# canbus-proto2.net
KiCad netlist of a schematic drawn in EAGLE
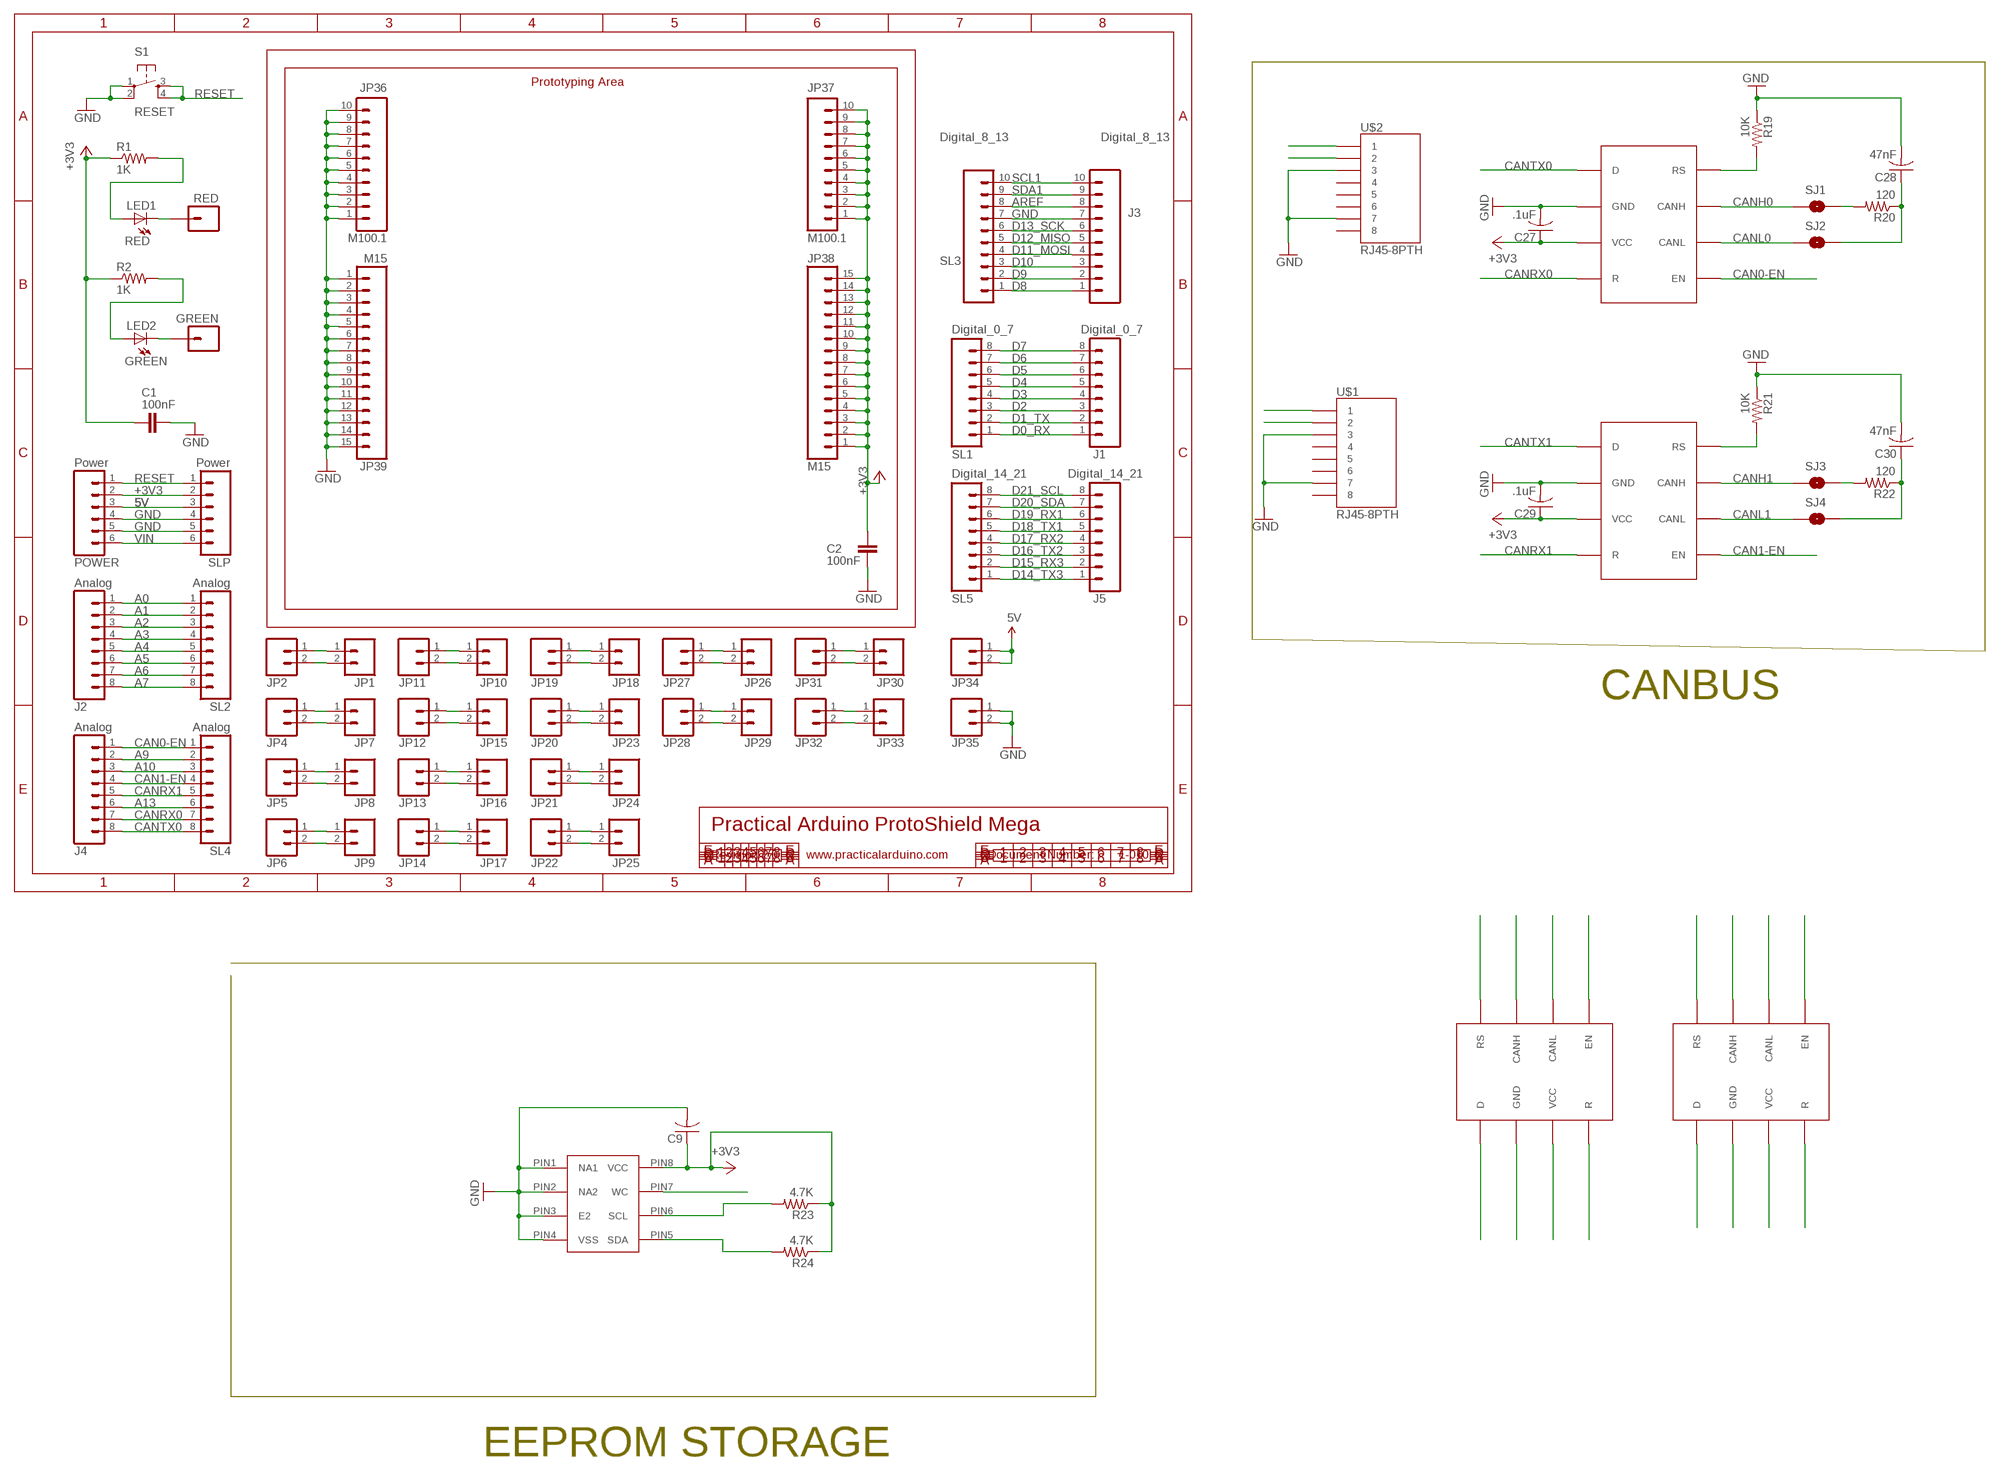
[diagram p0: schematic, sheet 1]

(export (version "E")
  (design (tool "Eeschema 10.0.6"))
  (components
    (comp (ref "C1")
      (value "100nF")
      (footprint "eagle-import:0603-CAP")
      (libsource (lib "eagle-import") (part "CAP0603-CAP"))
    )
    (comp (ref "C2")
      (value "100nF")
      (footprint "eagle-import:0603-CAP")
      (libsource (lib "eagle-import") (part "CAP0603-CAP"))
    )
    (comp (ref "C9")
      (value "C-USC0603")
      (footprint "eagle-import:C0603")
      (libsource (lib "eagle-import") (part "C-USC0603"))
    )
    (comp (ref "C27")
      (value ".1uF")
      (footprint "eagle-import:C0603")
      (libsource (lib "eagle-import") (part "C-USC0603"))
    )
    (comp (ref "C28")
      (value "47nF")
      (footprint "eagle-import:C0603")
      (libsource (lib "eagle-import") (part "C-USC0603"))
    )
    (comp (ref "C29")
      (value ".1uF")
      (footprint "eagle-import:C0603")
      (libsource (lib "eagle-import") (part "C-USC0603"))
    )
    (comp (ref "C30")
      (value "47nF")
      (footprint "eagle-import:C0603")
      (libsource (lib "eagle-import") (part "C-USC0603"))
    )
    (comp (ref "GREEN")
      (value "M01PTH")
      (footprint "eagle-import:1X01")
      (libsource (lib "eagle-import") (part "M01PTH"))
    )
    (comp (ref "J1")
      (value "Digital_0_7")
      (footprint "eagle-import:1X08")
      (libsource (lib "eagle-import") (part "M08"))
    )
    (comp (ref "J2")
      (value "Analog")
      (footprint "eagle-import:1X08")
      (libsource (lib "eagle-import") (part "M08"))
    )
    (comp (ref "J3")
      (value "Digital_8_13")
      (footprint "eagle-import:1X10")
      (libsource (lib "eagle-import") (part "M10{dblquote}"))
    )
    (comp (ref "J4")
      (value "Analog")
      (footprint "eagle-import:1X08")
      (libsource (lib "eagle-import") (part "M08"))
    )
    (comp (ref "J5")
      (value "Digital_14_21")
      (footprint "eagle-import:1X08")
      (libsource (lib "eagle-import") (part "M08"))
    )
    (comp (ref "JP1")
      (value "M02PTH")
      (footprint "eagle-import:1X02")
      (libsource (lib "eagle-import") (part "M02PTH"))
    )
    (comp (ref "JP2")
      (value "M02PTH")
      (footprint "eagle-import:1X02")
      (libsource (lib "eagle-import") (part "M02PTH"))
    )
    (comp (ref "JP4")
      (value "M02PTH")
      (footprint "eagle-import:1X02")
      (libsource (lib "eagle-import") (part "M02PTH"))
    )
    (comp (ref "JP5")
      (value "M02PTH")
      (footprint "eagle-import:1X02")
      (libsource (lib "eagle-import") (part "M02PTH"))
    )
    (comp (ref "JP6")
      (value "M02PTH")
      (footprint "eagle-import:1X02")
      (libsource (lib "eagle-import") (part "M02PTH"))
    )
    (comp (ref "JP7")
      (value "M02PTH")
      (footprint "eagle-import:1X02")
      (libsource (lib "eagle-import") (part "M02PTH"))
    )
    (comp (ref "JP8")
      (value "M02PTH")
      (footprint "eagle-import:1X02")
      (libsource (lib "eagle-import") (part "M02PTH"))
    )
    (comp (ref "JP9")
      (value "M02PTH")
      (footprint "eagle-import:1X02")
      (libsource (lib "eagle-import") (part "M02PTH"))
    )
    (comp (ref "JP10")
      (value "M02PTH")
      (footprint "eagle-import:1X02")
      (libsource (lib "eagle-import") (part "M02PTH"))
    )
    (comp (ref "JP11")
      (value "M02PTH")
      (footprint "eagle-import:1X02")
      (libsource (lib "eagle-import") (part "M02PTH"))
    )
    (comp (ref "JP12")
      (value "M02PTH")
      (footprint "eagle-import:1X02")
      (libsource (lib "eagle-import") (part "M02PTH"))
    )
    (comp (ref "JP13")
      (value "M02PTH")
      (footprint "eagle-import:1X02")
      (libsource (lib "eagle-import") (part "M02PTH"))
    )
    (comp (ref "JP14")
      (value "M02PTH")
      (footprint "eagle-import:1X02")
      (libsource (lib "eagle-import") (part "M02PTH"))
    )
    (comp (ref "JP15")
      (value "M02PTH")
      (footprint "eagle-import:1X02")
      (libsource (lib "eagle-import") (part "M02PTH"))
    )
    (comp (ref "JP16")
      (value "M02PTH")
      (footprint "eagle-import:1X02")
      (libsource (lib "eagle-import") (part "M02PTH"))
    )
    (comp (ref "JP17")
      (value "M02PTH")
      (footprint "eagle-import:1X02")
      (libsource (lib "eagle-import") (part "M02PTH"))
    )
    (comp (ref "JP18")
      (value "M02PTH")
      (footprint "eagle-import:1X02")
      (libsource (lib "eagle-import") (part "M02PTH"))
    )
    (comp (ref "JP19")
      (value "M02PTH")
      (footprint "eagle-import:1X02")
      (libsource (lib "eagle-import") (part "M02PTH"))
    )
    (comp (ref "JP20")
      (value "M02PTH")
      (footprint "eagle-import:1X02")
      (libsource (lib "eagle-import") (part "M02PTH"))
    )
    (comp (ref "JP21")
      (value "M02PTH")
      (footprint "eagle-import:1X02")
      (libsource (lib "eagle-import") (part "M02PTH"))
    )
    (comp (ref "JP22")
      (value "M02PTH")
      (footprint "eagle-import:1X02")
      (libsource (lib "eagle-import") (part "M02PTH"))
    )
    (comp (ref "JP23")
      (value "M02PTH")
      (footprint "eagle-import:1X02")
      (libsource (lib "eagle-import") (part "M02PTH"))
    )
    (comp (ref "JP24")
      (value "M02PTH")
      (footprint "eagle-import:1X02")
      (libsource (lib "eagle-import") (part "M02PTH"))
    )
    (comp (ref "JP25")
      (value "M02PTH")
      (footprint "eagle-import:1X02")
      (libsource (lib "eagle-import") (part "M02PTH"))
    )
    (comp (ref "JP26")
      (value "M02PTH")
      (footprint "eagle-import:1X02")
      (libsource (lib "eagle-import") (part "M02PTH"))
    )
    (comp (ref "JP27")
      (value "M02PTH")
      (footprint "eagle-import:1X02")
      (libsource (lib "eagle-import") (part "M02PTH"))
    )
    (comp (ref "JP28")
      (value "M02PTH")
      (footprint "eagle-import:1X02")
      (libsource (lib "eagle-import") (part "M02PTH"))
    )
    (comp (ref "JP29")
      (value "M02PTH")
      (footprint "eagle-import:1X02")
      (libsource (lib "eagle-import") (part "M02PTH"))
    )
    (comp (ref "JP30")
      (value "M02PTH")
      (footprint "eagle-import:1X02")
      (libsource (lib "eagle-import") (part "M02PTH"))
    )
    (comp (ref "JP31")
      (value "M02PTH")
      (footprint "eagle-import:1X02")
      (libsource (lib "eagle-import") (part "M02PTH"))
    )
    (comp (ref "JP32")
      (value "M02PTH")
      (footprint "eagle-import:1X02")
      (libsource (lib "eagle-import") (part "M02PTH"))
    )
    (comp (ref "JP33")
      (value "M02PTH")
      (footprint "eagle-import:1X02")
      (libsource (lib "eagle-import") (part "M02PTH"))
    )
    (comp (ref "JP34")
      (value "M02PTH")
      (footprint "eagle-import:1X02")
      (libsource (lib "eagle-import") (part "M02PTH"))
    )
    (comp (ref "JP35")
      (value "M02PTH")
      (footprint "eagle-import:1X02")
      (libsource (lib "eagle-import") (part "M02PTH"))
    )
    (comp (ref "JP36")
      (value "M100.1")
      (footprint "eagle-import:1X10@1")
      (libsource (lib "eagle-import") (part "M100.1"))
    )
    (comp (ref "JP37")
      (value "M100.1")
      (footprint "eagle-import:1X10@1")
      (libsource (lib "eagle-import") (part "M100.1"))
    )
    (comp (ref "JP38")
      (value "M15")
      (footprint "eagle-import:1X15")
      (libsource (lib "eagle-import") (part "M15"))
    )
    (comp (ref "JP39")
      (value "M15")
      (footprint "eagle-import:1X15")
      (libsource (lib "eagle-import") (part "M15"))
    )
    (comp (ref "LED1")
      (value "RED")
      (footprint "eagle-import:LED-0603")
      (libsource (lib "eagle-import") (part "LED-RED0603"))
    )
    (comp (ref "LED2")
      (value "GREEN")
      (footprint "eagle-import:LED-0603")
      (libsource (lib "eagle-import") (part "LED-GREEN0603"))
    )
    (comp (ref "POWER")
      (value "Power")
      (footprint "eagle-import:1X06")
      (libsource (lib "eagle-import") (part "M06SIP"))
    )
    (comp (ref "R1")
      (value "1K")
      (footprint "eagle-import:R0603")
      (libsource (lib "eagle-import") (part "R-US_R0603"))
    )
    (comp (ref "R2")
      (value "1K")
      (footprint "eagle-import:R0603")
      (libsource (lib "eagle-import") (part "R-US_R0603"))
    )
    (comp (ref "R19")
      (value "10K")
      (footprint "eagle-import:R0603")
      (libsource (lib "eagle-import") (part "R-US_R0603"))
    )
    (comp (ref "R20")
      (value "120")
      (footprint "eagle-import:R0603")
      (libsource (lib "eagle-import") (part "R-US_R0603"))
    )
    (comp (ref "R21")
      (value "10K")
      (footprint "eagle-import:R0603")
      (libsource (lib "eagle-import") (part "R-US_R0603"))
    )
    (comp (ref "R22")
      (value "120")
      (footprint "eagle-import:R0603")
      (libsource (lib "eagle-import") (part "R-US_R0603"))
    )
    (comp (ref "R23")
      (value "4.7K")
      (footprint "eagle-import:R0603")
      (libsource (lib "eagle-import") (part "R-US_R0603"))
    )
    (comp (ref "R24")
      (value "4.7K")
      (footprint "eagle-import:R0603")
      (libsource (lib "eagle-import") (part "R-US_R0603"))
    )
    (comp (ref "RED")
      (value "M01PTH")
      (footprint "eagle-import:1X01")
      (libsource (lib "eagle-import") (part "M01PTH"))
    )
    (comp (ref "S1")
      (value "RESET")
      (footprint "eagle-import:TACTILE-PTH")
      (libsource (lib "eagle-import") (part "TAC_SWITCHPTH"))
    )
    (comp (ref "SJ1")
      (value "SOLDERJUMPERNO")
      (footprint "eagle-import:SJ_2S-NO")
      (libsource (lib "eagle-import") (part "SOLDERJUMPERNO"))
    )
    (comp (ref "SJ2")
      (value "SOLDERJUMPERNO")
      (footprint "eagle-import:SJ_2S-NO")
      (libsource (lib "eagle-import") (part "SOLDERJUMPERNO"))
    )
    (comp (ref "SJ3")
      (value "SOLDERJUMPERNO")
      (footprint "eagle-import:SJ_2S-NO")
      (libsource (lib "eagle-import") (part "SOLDERJUMPERNO"))
    )
    (comp (ref "SJ4")
      (value "SOLDERJUMPERNO")
      (footprint "eagle-import:SJ_2S-NO")
      (libsource (lib "eagle-import") (part "SOLDERJUMPERNO"))
    )
    (comp (ref "SL1")
      (value "Digital_0_7")
      (footprint "eagle-import:1X08")
      (libsource (lib "eagle-import") (part "M08"))
    )
    (comp (ref "SL2")
      (value "Analog")
      (footprint "eagle-import:1X08")
      (libsource (lib "eagle-import") (part "M08"))
    )
    (comp (ref "SL3")
      (value "Digital_8_13")
      (footprint "eagle-import:1X10")
      (libsource (lib "eagle-import") (part "M10{dblquote}"))
    )
    (comp (ref "SL4")
      (value "Analog")
      (footprint "eagle-import:1X08")
      (libsource (lib "eagle-import") (part "M08"))
    )
    (comp (ref "SL5")
      (value "Digital_14_21")
      (footprint "eagle-import:1X08")
      (libsource (lib "eagle-import") (part "M08"))
    )
    (comp (ref "SLP")
      (value "Power")
      (footprint "eagle-import:1X06")
      (libsource (lib "eagle-import") (part "M06SIP"))
    )
    (comp (ref "U$1")
      (value "RJ45-8PTH")
      (footprint "eagle-import:RJ45-8")
      (libsource (lib "eagle-import") (part "RJ45-8PTH"))
    )
    (comp (ref "U$2")
      (value "RJ45-8PTH")
      (footprint "eagle-import:RJ45-8")
      (libsource (lib "eagle-import") (part "RJ45-8PTH"))
    )
    (comp (ref "U$3")
      (value "SN65HVD234")
      (footprint "eagle-import:SOIC8")
      (libsource (lib "eagle-import") (part "SN65HVD234"))
    )
    (comp (ref "U$4")
      (value "SN65HVD234")
      (footprint "eagle-import:SOIC8")
      (libsource (lib "eagle-import") (part "SN65HVD234"))
    )
    (comp (ref "U$6")
      (value "M24M02-DRMN6TP")
      (footprint "eagle-import:SOIC8")
      (libsource (lib "eagle-import") (part "M24M02-DRMN6TP"))
    )
    (comp (ref "U$7")
      (value "SN65HVD234")
      (footprint "eagle-import:SOIC8")
      (libsource (lib "eagle-import") (part "SN65HVD234"))
    )
    (comp (ref "U$8")
      (value "SN65HVD234")
      (footprint "eagle-import:SOIC8")
      (libsource (lib "eagle-import") (part "SN65HVD234"))
    )
  )
  (nets
    (net (code "1") (name "+3V3") (class "Default")
      (node (ref "C1") (pin "1") (pinfunction "1_1") (pintype "passive"))
      (node (ref "C2") (pin "1") (pinfunction "1_1") (pintype "passive"))
      (node (ref "C27") (pin "1") (pinfunction "1_1") (pintype "passive"))
      (node (ref "C29") (pin "1") (pinfunction "1_1") (pintype "passive"))
      (node (ref "C9") (pin "1") (pinfunction "1_1") (pintype "passive"))
      (node (ref "JP37") (pin "1") (pinfunction "1_1") (pintype "passive"))
      (node (ref "JP37") (pin "10") (pinfunction "10_10") (pintype "passive"))
      (node (ref "JP37") (pin "2") (pinfunction "2_2") (pintype "passive"))
      (node (ref "JP37") (pin "3") (pinfunction "3_3") (pintype "passive"))
      (node (ref "JP37") (pin "4") (pinfunction "4_4") (pintype "passive"))
      (node (ref "JP37") (pin "5") (pinfunction "5_5") (pintype "passive"))
      (node (ref "JP37") (pin "6") (pinfunction "6_6") (pintype "passive"))
      (node (ref "JP37") (pin "7") (pinfunction "7_7") (pintype "passive"))
      (node (ref "JP37") (pin "8") (pinfunction "8_8") (pintype "passive"))
      (node (ref "JP37") (pin "9") (pinfunction "9_9") (pintype "passive"))
      (node (ref "JP38") (pin "1") (pinfunction "1_1") (pintype "passive"))
      (node (ref "JP38") (pin "10") (pinfunction "10_10") (pintype "passive"))
      (node (ref "JP38") (pin "11") (pinfunction "11_11") (pintype "passive"))
      (node (ref "JP38") (pin "12") (pinfunction "12_12") (pintype "passive"))
      (node (ref "JP38") (pin "13") (pinfunction "13_13") (pintype "passive"))
      (node (ref "JP38") (pin "14") (pinfunction "14_14") (pintype "passive"))
      (node (ref "JP38") (pin "15") (pinfunction "15_15") (pintype "passive"))
      (node (ref "JP38") (pin "2") (pinfunction "2_2") (pintype "passive"))
      (node (ref "JP38") (pin "3") (pinfunction "3_3") (pintype "passive"))
      (node (ref "JP38") (pin "4") (pinfunction "4_4") (pintype "passive"))
      (node (ref "JP38") (pin "5") (pinfunction "5_5") (pintype "passive"))
      (node (ref "JP38") (pin "6") (pinfunction "6_6") (pintype "passive"))
      (node (ref "JP38") (pin "7") (pinfunction "7_7") (pintype "passive"))
      (node (ref "JP38") (pin "8") (pinfunction "8_8") (pintype "passive"))
      (node (ref "JP38") (pin "9") (pinfunction "9_9") (pintype "passive"))
      (node (ref "POWER") (pin "2") (pinfunction "2_2") (pintype "passive"))
      (node (ref "R1") (pin "1") (pinfunction "1_1") (pintype "passive"))
      (node (ref "R2") (pin "1") (pinfunction "1_1") (pintype "passive"))
      (node (ref "R23") (pin "1") (pinfunction "1_1") (pintype "passive"))
      (node (ref "R24") (pin "1") (pinfunction "1_1") (pintype "passive"))
      (node (ref "SLP") (pin "2") (pinfunction "2_2") (pintype "passive"))
      (node (ref "U$6") (pin "PIN8") (pinfunction "VCC_PIN8") (pintype "bidirectional"))
      (node (ref "U$7") (pin "PIN3") (pinfunction "VCC_PIN3") (pintype "bidirectional"))
      (node (ref "U$8") (pin "PIN3") (pinfunction "VCC_PIN3") (pintype "bidirectional"))
    )
    (net (code "2") (name "/A0") (class "Default")
      (node (ref "J2") (pin "1") (pinfunction "1_1") (pintype "passive"))
      (node (ref "SL2") (pin "1") (pinfunction "1_1") (pintype "passive"))
    )
    (net (code "3") (name "/A1") (class "Default")
      (node (ref "J2") (pin "2") (pinfunction "2_2") (pintype "passive"))
      (node (ref "SL2") (pin "2") (pinfunction "2_2") (pintype "passive"))
    )
    (net (code "4") (name "/A2") (class "Default")
      (node (ref "J2") (pin "3") (pinfunction "3_3") (pintype "passive"))
      (node (ref "SL2") (pin "3") (pinfunction "3_3") (pintype "passive"))
    )
    (net (code "5") (name "/A3") (class "Default")
      (node (ref "J2") (pin "4") (pinfunction "4_4") (pintype "passive"))
      (node (ref "SL2") (pin "4") (pinfunction "4_4") (pintype "passive"))
    )
    (net (code "6") (name "/A4") (class "Default")
      (node (ref "J2") (pin "5") (pinfunction "5_5") (pintype "passive"))
      (node (ref "SL2") (pin "5") (pinfunction "5_5") (pintype "passive"))
    )
    (net (code "7") (name "/A5") (class "Default")
      (node (ref "J2") (pin "6") (pinfunction "6_6") (pintype "passive"))
      (node (ref "SL2") (pin "6") (pinfunction "6_6") (pintype "passive"))
    )
    (net (code "8") (name "/A6") (class "Default")
      (node (ref "J2") (pin "7") (pinfunction "7_7") (pintype "passive"))
      (node (ref "SL2") (pin "7") (pinfunction "7_7") (pintype "passive"))
    )
    (net (code "9") (name "/A7") (class "Default")
      (node (ref "J2") (pin "8") (pinfunction "8_8") (pintype "passive"))
      (node (ref "SL2") (pin "8") (pinfunction "8_8") (pintype "passive"))
    )
    (net (code "10") (name "/A9") (class "Default")
      (node (ref "J4") (pin "2") (pinfunction "2_2") (pintype "passive"))
      (node (ref "SL4") (pin "2") (pinfunction "2_2") (pintype "passive"))
    )
    (net (code "11") (name "/A10") (class "Default")
      (node (ref "J4") (pin "3") (pinfunction "3_3") (pintype "passive"))
      (node (ref "SL4") (pin "3") (pinfunction "3_3") (pintype "passive"))
    )
    (net (code "12") (name "/A13") (class "Default")
      (node (ref "J4") (pin "6") (pinfunction "6_6") (pintype "passive"))
      (node (ref "SL4") (pin "6") (pinfunction "6_6") (pintype "passive"))
    )
    (net (code "13") (name "/AREF") (class "Default")
      (node (ref "J3") (pin "8") (pinfunction "8_8") (pintype "passive"))
      (node (ref "SL3") (pin "8") (pinfunction "8_8") (pintype "passive"))
    )
    (net (code "14") (name "/CAN0-EN") (class "Default")
      (node (ref "J4") (pin "1") (pinfunction "1_1") (pintype "passive"))
      (node (ref "SL4") (pin "1") (pinfunction "1_1") (pintype "passive"))
      (node (ref "U$7") (pin "PIN5") (pinfunction "EN_PIN5") (pintype "bidirectional"))
    )
    (net (code "15") (name "/CAN1-EN") (class "Default")
      (node (ref "J4") (pin "4") (pinfunction "4_4") (pintype "passive"))
      (node (ref "SL4") (pin "4") (pinfunction "4_4") (pintype "passive"))
      (node (ref "U$8") (pin "PIN5") (pinfunction "EN_PIN5") (pintype "bidirectional"))
    )
    (net (code "16") (name "/CANH0") (class "Default")
      (node (ref "SJ1") (pin "1") (pinfunction "1_1") (pintype "passive"))
      (node (ref "U$2") (pin "1") (pinfunction "1_1") (pintype "bidirectional"))
      (node (ref "U$7") (pin "PIN7") (pinfunction "CANH_PIN7") (pintype "bidirectional"))
    )
    (net (code "17") (name "/CANH1") (class "Default")
      (node (ref "SJ3") (pin "1") (pinfunction "1_1") (pintype "passive"))
      (node (ref "U$1") (pin "1") (pinfunction "1_1") (pintype "bidirectional"))
      (node (ref "U$8") (pin "PIN7") (pinfunction "CANH_PIN7") (pintype "bidirectional"))
    )
    (net (code "18") (name "/CANL0") (class "Default")
      (node (ref "SJ2") (pin "1") (pinfunction "1_1") (pintype "passive"))
      (node (ref "U$2") (pin "2") (pinfunction "2_2") (pintype "bidirectional"))
      (node (ref "U$7") (pin "PIN6") (pinfunction "CANL_PIN6") (pintype "bidirectional"))
    )
    (net (code "19") (name "/CANL1") (class "Default")
      (node (ref "SJ4") (pin "1") (pinfunction "1_1") (pintype "passive"))
      (node (ref "U$1") (pin "2") (pinfunction "2_2") (pintype "bidirectional"))
      (node (ref "U$8") (pin "PIN6") (pinfunction "CANL_PIN6") (pintype "bidirectional"))
    )
    (net (code "20") (name "/CANRX0") (class "Default")
      (node (ref "J4") (pin "7") (pinfunction "7_7") (pintype "passive"))
      (node (ref "SL4") (pin "7") (pinfunction "7_7") (pintype "passive"))
      (node (ref "U$7") (pin "PIN4") (pinfunction "R_PIN4") (pintype "bidirectional"))
    )
    (net (code "21") (name "/CANRX1") (class "Default")
      (node (ref "J4") (pin "5") (pinfunction "5_5") (pintype "passive"))
      (node (ref "SL4") (pin "5") (pinfunction "5_5") (pintype "passive"))
      (node (ref "U$8") (pin "PIN4") (pinfunction "R_PIN4") (pintype "bidirectional"))
    )
    (net (code "22") (name "/CANTX0") (class "Default")
      (node (ref "J4") (pin "8") (pinfunction "8_8") (pintype "passive"))
      (node (ref "SL4") (pin "8") (pinfunction "8_8") (pintype "passive"))
      (node (ref "U$7") (pin "PIN1") (pinfunction "D_PIN1") (pintype "bidirectional"))
    )
    (net (code "23") (name "/CANTX1") (class "Default")
      (node (ref "JP32") (pin "2") (pinfunction "2_2") (pintype "passive"))
      (node (ref "JP33") (pin "2") (pinfunction "2_2") (pintype "passive"))
      (node (ref "U$8") (pin "PIN1") (pinfunction "D_PIN1") (pintype "bidirectional"))
    )
    (net (code "24") (name "/D0_RX") (class "Default")
      (node (ref "J1") (pin "1") (pinfunction "1_1") (pintype "passive"))
      (node (ref "SL1") (pin "1") (pinfunction "1_1") (pintype "passive"))
    )
    (net (code "25") (name "/D1_TX") (class "Default")
      (node (ref "J1") (pin "2") (pinfunction "2_2") (pintype "passive"))
      (node (ref "SL1") (pin "2") (pinfunction "2_2") (pintype "passive"))
    )
    (net (code "26") (name "/D2") (class "Default")
      (node (ref "J1") (pin "3") (pinfunction "3_3") (pintype "passive"))
      (node (ref "SL1") (pin "3") (pinfunction "3_3") (pintype "passive"))
    )
    (net (code "27") (name "/D3") (class "Default")
      (node (ref "J1") (pin "4") (pinfunction "4_4") (pintype "passive"))
      (node (ref "SL1") (pin "4") (pinfunction "4_4") (pintype "passive"))
    )
    (net (code "28") (name "/D4") (class "Default")
      (node (ref "J1") (pin "5") (pinfunction "5_5") (pintype "passive"))
      (node (ref "SL1") (pin "5") (pinfunction "5_5") (pintype "passive"))
    )
    (net (code "29") (name "/D5") (class "Default")
      (node (ref "J1") (pin "6") (pinfunction "6_6") (pintype "passive"))
      (node (ref "SL1") (pin "6") (pinfunction "6_6") (pintype "passive"))
    )
    (net (code "30") (name "/D6") (class "Default")
      (node (ref "J1") (pin "7") (pinfunction "7_7") (pintype "passive"))
      (node (ref "SL1") (pin "7") (pinfunction "7_7") (pintype "passive"))
    )
    (net (code "31") (name "/D7") (class "Default")
      (node (ref "J1") (pin "8") (pinfunction "8_8") (pintype "passive"))
      (node (ref "SL1") (pin "8") (pinfunction "8_8") (pintype "passive"))
    )
    (net (code "32") (name "/D8") (class "Default")
      (node (ref "J3") (pin "1") (pinfunction "1_1") (pintype "passive"))
      (node (ref "SL3") (pin "1") (pinfunction "1_1") (pintype "passive"))
    )
    (net (code "33") (name "/D9") (class "Default")
      (node (ref "J3") (pin "2") (pinfunction "2_2") (pintype "passive"))
      (node (ref "SL3") (pin "2") (pinfunction "2_2") (pintype "passive"))
    )
    (net (code "34") (name "/D10") (class "Default")
      (node (ref "J3") (pin "3") (pinfunction "3_3") (pintype "passive"))
      (node (ref "SL3") (pin "3") (pinfunction "3_3") (pintype "passive"))
    )
    (net (code "35") (name "/D11_MOSI") (class "Default")
      (node (ref "J3") (pin "4") (pinfunction "4_4") (pintype "passive"))
      (node (ref "SL3") (pin "4") (pinfunction "4_4") (pintype "passive"))
    )
    (net (code "36") (name "/D12_MISO") (class "Default")
      (node (ref "J3") (pin "5") (pinfunction "5_5") (pintype "passive"))
      (node (ref "SL3") (pin "5") (pinfunction "5_5") (pintype "passive"))
    )
    (net (code "37") (name "/D13_SCK") (class "Default")
      (node (ref "J3") (pin "6") (pinfunction "6_6") (pintype "passive"))
      (node (ref "SL3") (pin "6") (pinfunction "6_6") (pintype "passive"))
    )
    (net (code "38") (name "/D14_TX3") (class "Default")
      (node (ref "J5") (pin "1") (pinfunction "1_1") (pintype "passive"))
      (node (ref "SL5") (pin "1") (pinfunction "1_1") (pintype "passive"))
    )
    (net (code "39") (name "/D15_RX3") (class "Default")
      (node (ref "J5") (pin "2") (pinfunction "2_2") (pintype "passive"))
      (node (ref "SL5") (pin "2") (pinfunction "2_2") (pintype "passive"))
    )
    (net (code "40") (name "/D16_TX2") (class "Default")
      (node (ref "J5") (pin "3") (pinfunction "3_3") (pintype "passive"))
      (node (ref "SL5") (pin "3") (pinfunction "3_3") (pintype "passive"))
    )
    (net (code "41") (name "/D17_RX2") (class "Default")
      (node (ref "J5") (pin "4") (pinfunction "4_4") (pintype "passive"))
      (node (ref "SL5") (pin "4") (pinfunction "4_4") (pintype "passive"))
    )
    (net (code "42") (name "/D18_TX1") (class "Default")
      (node (ref "J5") (pin "5") (pinfunction "5_5") (pintype "passive"))
      (node (ref "SL5") (pin "5") (pinfunction "5_5") (pintype "passive"))
      (node (ref "U$6") (pin "PIN7") (pinfunction "WC_PIN7") (pintype "bidirectional"))
    )
    (net (code "43") (name "/D19_RX1") (class "Default")
      (node (ref "J5") (pin "6") (pinfunction "6_6") (pintype "passive"))
      (node (ref "SL5") (pin "6") (pinfunction "6_6") (pintype "passive"))
    )
    (net (code "44") (name "/D20_SDA") (class "Default")
      (node (ref "J5") (pin "7") (pinfunction "7_7") (pintype "passive"))
      (node (ref "R24") (pin "2") (pinfunction "2_2") (pintype "passive"))
      (node (ref "SL5") (pin "7") (pinfunction "7_7") (pintype "passive"))
      (node (ref "U$6") (pin "PIN5") (pinfunction "SDA_PIN5") (pintype "bidirectional"))
    )
    (net (code "45") (name "/D21_SCL") (class "Default")
      (node (ref "J5") (pin "8") (pinfunction "8_8") (pintype "passive"))
      (node (ref "R23") (pin "2") (pinfunction "2_2") (pintype "passive"))
      (node (ref "SL5") (pin "8") (pinfunction "8_8") (pintype "passive"))
      (node (ref "U$6") (pin "PIN6") (pinfunction "SCL_PIN6") (pintype "bidirectional"))
    )
    (net (code "46") (name "/RESET") (class "Default")
      (node (ref "POWER") (pin "1") (pinfunction "1_1") (pintype "passive"))
      (node (ref "S1") (pin "3") (pinfunction "3_3") (pintype "passive"))
      (node (ref "S1") (pin "4") (pinfunction "4_4") (pintype "passive"))
      (node (ref "SLP") (pin "1") (pinfunction "1_1") (pintype "passive"))
    )
    (net (code "47") (name "/SCL1") (class "Default")
      (node (ref "J3") (pin "10") (pinfunction "10_10") (pintype "passive"))
      (node (ref "SL3") (pin "10") (pinfunction "10_10") (pintype "passive"))
    )
    (net (code "48") (name "/SDA1") (class "Default")
      (node (ref "J3") (pin "9") (pinfunction "9_9") (pintype "passive"))
      (node (ref "SL3") (pin "9") (pinfunction "9_9") (pintype "passive"))
    )
    (net (code "49") (name "/VIN") (class "Default")
      (node (ref "POWER") (pin "6") (pinfunction "6_6") (pintype "passive"))
      (node (ref "SLP") (pin "6") (pinfunction "6_6") (pintype "passive"))
    )
    (net (code "50") (name "5V") (class "Default")
      (node (ref "JP34") (pin "1") (pinfunction "1_1") (pintype "passive"))
      (node (ref "JP34") (pin "2") (pinfunction "2_2") (pintype "passive"))
      (node (ref "POWER") (pin "3") (pinfunction "3_3") (pintype "passive"))
      (node (ref "SLP") (pin "3") (pinfunction "3_3") (pintype "passive"))
    )
    (net (code "51") (name "GND") (class "Default")
      (node (ref "C1") (pin "2") (pinfunction "2_2") (pintype "passive"))
      (node (ref "C2") (pin "2") (pinfunction "2_2") (pintype "passive"))
      (node (ref "C27") (pin "2") (pinfunction "2_2") (pintype "passive"))
      (node (ref "C28") (pin "2") (pinfunction "2_2") (pintype "passive"))
      (node (ref "C29") (pin "2") (pinfunction "2_2") (pintype "passive"))
      (node (ref "C30") (pin "2") (pinfunction "2_2") (pintype "passive"))
      (node (ref "C9") (pin "2") (pinfunction "2_2") (pintype "passive"))
      (node (ref "J3") (pin "7") (pinfunction "7_7") (pintype "passive"))
      (node (ref "JP35") (pin "1") (pinfunction "1_1") (pintype "passive"))
      (node (ref "JP35") (pin "2") (pinfunction "2_2") (pintype "passive"))
      (node (ref "JP36") (pin "1") (pinfunction "1_1") (pintype "passive"))
      (node (ref "JP36") (pin "10") (pinfunction "10_10") (pintype "passive"))
      (node (ref "JP36") (pin "2") (pinfunction "2_2") (pintype "passive"))
      (node (ref "JP36") (pin "3") (pinfunction "3_3") (pintype "passive"))
      (node (ref "JP36") (pin "4") (pinfunction "4_4") (pintype "passive"))
      (node (ref "JP36") (pin "5") (pinfunction "5_5") (pintype "passive"))
      (node (ref "JP36") (pin "6") (pinfunction "6_6") (pintype "passive"))
      (node (ref "JP36") (pin "7") (pinfunction "7_7") (pintype "passive"))
      (node (ref "JP36") (pin "8") (pinfunction "8_8") (pintype "passive"))
      (node (ref "JP36") (pin "9") (pinfunction "9_9") (pintype "passive"))
      (node (ref "JP39") (pin "1") (pinfunction "1_1") (pintype "passive"))
      (node (ref "JP39") (pin "10") (pinfunction "10_10") (pintype "passive"))
      (node (ref "JP39") (pin "11") (pinfunction "11_11") (pintype "passive"))
      (node (ref "JP39") (pin "12") (pinfunction "12_12") (pintype "passive"))
      (node (ref "JP39") (pin "13") (pinfunction "13_13") (pintype "passive"))
      (node (ref "JP39") (pin "14") (pinfunction "14_14") (pintype "passive"))
      (node (ref "JP39") (pin "15") (pinfunction "15_15") (pintype "passive"))
      (node (ref "JP39") (pin "2") (pinfunction "2_2") (pintype "passive"))
      (node (ref "JP39") (pin "3") (pinfunction "3_3") (pintype "passive"))
      (node (ref "JP39") (pin "4") (pinfunction "4_4") (pintype "passive"))
      (node (ref "JP39") (pin "5") (pinfunction "5_5") (pintype "passive"))
      (node (ref "JP39") (pin "6") (pinfunction "6_6") (pintype "passive"))
      (node (ref "JP39") (pin "7") (pinfunction "7_7") (pintype "passive"))
      (node (ref "JP39") (pin "8") (pinfunction "8_8") (pintype "passive"))
      (node (ref "JP39") (pin "9") (pinfunction "9_9") (pintype "passive"))
      (node (ref "POWER") (pin "4") (pinfunction "4_4") (pintype "passive"))
      (node (ref "POWER") (pin "5") (pinfunction "5_5") (pintype "passive"))
      (node (ref "R19") (pin "1") (pinfunction "1_1") (pintype "passive"))
      (node (ref "R21") (pin "1") (pinfunction "1_1") (pintype "passive"))
      (node (ref "S1") (pin "1") (pinfunction "1_1") (pintype "passive"))
      (node (ref "S1") (pin "2") (pinfunction "2_2") (pintype "passive"))
      (node (ref "SL3") (pin "7") (pinfunction "7_7") (pintype "passive"))
      (node (ref "SLP") (pin "4") (pinfunction "4_4") (pintype "passive"))
      (node (ref "SLP") (pin "5") (pinfunction "5_5") (pintype "passive"))
      (node (ref "U$1") (pin "3") (pinfunction "3_3") (pintype "bidirectional"))
      (node (ref "U$1") (pin "7") (pinfunction "7_7") (pintype "bidirectional"))
      (node (ref "U$2") (pin "3") (pinfunction "3_3") (pintype "bidirectional"))
      (node (ref "U$2") (pin "7") (pinfunction "7_7") (pintype "bidirectional"))
      (node (ref "U$6") (pin "PIN1") (pinfunction "NA1_PIN1") (pintype "bidirectional"))
      (node (ref "U$6") (pin "PIN2") (pinfunction "NA2_PIN2") (pintype "bidirectional"))
      (node (ref "U$6") (pin "PIN3") (pinfunction "E2_PIN3") (pintype "bidirectional"))
      (node (ref "U$6") (pin "PIN4") (pinfunction "VSS_PIN4") (pintype "bidirectional"))
      (node (ref "U$7") (pin "PIN2") (pinfunction "GND_PIN2") (pintype "bidirectional"))
      (node (ref "U$8") (pin "PIN2") (pinfunction "GND_PIN2") (pintype "bidirectional"))
    )
    (net (code "52") (name "Net-(C28-Pad1)") (class "Default")
      (node (ref "C28") (pin "1") (pinfunction "1_1") (pintype "passive"))
      (node (ref "R20") (pin "1") (pinfunction "1_1") (pintype "passive"))
      (node (ref "SJ2") (pin "2") (pinfunction "2_2") (pintype "passive"))
    )
    (net (code "53") (name "Net-(C30-Pad1)") (class "Default")
      (node (ref "C30") (pin "1") (pinfunction "1_1") (pintype "passive"))
      (node (ref "R22") (pin "1") (pinfunction "1_1") (pintype "passive"))
      (node (ref "SJ4") (pin "2") (pinfunction "2_2") (pintype "passive"))
    )
    (net (code "54") (name "Net-(GREEN-Pad1)") (class "Default")
      (node (ref "GREEN") (pin "1") (pinfunction "1_1") (pintype "passive"))
      (node (ref "LED2") (pin "C") (pinfunction "C_C") (pintype "passive"))
    )
    (net (code "55") (name "Net-(JP1-Pad1)") (class "Default")
      (node (ref "JP1") (pin "1") (pinfunction "1_1") (pintype "passive"))
      (node (ref "JP2") (pin "1") (pinfunction "1_1") (pintype "passive"))
    )
    (net (code "56") (name "Net-(JP1-Pad2)") (class "Default")
      (node (ref "JP1") (pin "2") (pinfunction "2_2") (pintype "passive"))
      (node (ref "JP2") (pin "2") (pinfunction "2_2") (pintype "passive"))
    )
    (net (code "57") (name "Net-(JP4-Pad1)") (class "Default")
      (node (ref "JP4") (pin "1") (pinfunction "1_1") (pintype "passive"))
      (node (ref "JP7") (pin "1") (pinfunction "1_1") (pintype "passive"))
    )
    (net (code "58") (name "Net-(JP4-Pad2)") (class "Default")
      (node (ref "JP4") (pin "2") (pinfunction "2_2") (pintype "passive"))
      (node (ref "JP7") (pin "2") (pinfunction "2_2") (pintype "passive"))
    )
    (net (code "59") (name "Net-(JP5-Pad1)") (class "Default")
      (node (ref "JP5") (pin "1") (pinfunction "1_1") (pintype "passive"))
      (node (ref "JP8") (pin "1") (pinfunction "1_1") (pintype "passive"))
    )
    (net (code "60") (name "Net-(JP5-Pad2)") (class "Default")
      (node (ref "JP5") (pin "2") (pinfunction "2_2") (pintype "passive"))
      (node (ref "JP8") (pin "2") (pinfunction "2_2") (pintype "passive"))
    )
    (net (code "61") (name "Net-(JP6-Pad1)") (class "Default")
      (node (ref "JP6") (pin "1") (pinfunction "1_1") (pintype "passive"))
      (node (ref "JP9") (pin "1") (pinfunction "1_1") (pintype "passive"))
    )
    (net (code "62") (name "Net-(JP6-Pad2)") (class "Default")
      (node (ref "JP6") (pin "2") (pinfunction "2_2") (pintype "passive"))
      (node (ref "JP9") (pin "2") (pinfunction "2_2") (pintype "passive"))
    )
    (net (code "63") (name "Net-(JP10-Pad1)") (class "Default")
      (node (ref "JP10") (pin "1") (pinfunction "1_1") (pintype "passive"))
      (node (ref "JP11") (pin "1") (pinfunction "1_1") (pintype "passive"))
    )
    (net (code "64") (name "Net-(JP10-Pad2)") (class "Default")
      (node (ref "JP10") (pin "2") (pinfunction "2_2") (pintype "passive"))
      (node (ref "JP11") (pin "2") (pinfunction "2_2") (pintype "passive"))
    )
    (net (code "65") (name "Net-(JP12-Pad1)") (class "Default")
      (node (ref "JP12") (pin "1") (pinfunction "1_1") (pintype "passive"))
      (node (ref "JP15") (pin "1") (pinfunction "1_1") (pintype "passive"))
    )
    (net (code "66") (name "Net-(JP12-Pad2)") (class "Default")
      (node (ref "JP12") (pin "2") (pinfunction "2_2") (pintype "passive"))
      (node (ref "JP15") (pin "2") (pinfunction "2_2") (pintype "passive"))
    )
    (net (code "67") (name "Net-(JP13-Pad1)") (class "Default")
      (node (ref "JP13") (pin "1") (pinfunction "1_1") (pintype "passive"))
      (node (ref "JP16") (pin "1") (pinfunction "1_1") (pintype "passive"))
    )
    (net (code "68") (name "Net-(JP13-Pad2)") (class "Default")
      (node (ref "JP13") (pin "2") (pinfunction "2_2") (pintype "passive"))
      (node (ref "JP16") (pin "2") (pinfunction "2_2") (pintype "passive"))
    )
    (net (code "69") (name "Net-(JP14-Pad1)") (class "Default")
      (node (ref "JP14") (pin "1") (pinfunction "1_1") (pintype "passive"))
      (node (ref "JP17") (pin "1") (pinfunction "1_1") (pintype "passive"))
    )
    (net (code "70") (name "Net-(JP14-Pad2)") (class "Default")
      (node (ref "JP14") (pin "2") (pinfunction "2_2") (pintype "passive"))
      (node (ref "JP17") (pin "2") (pinfunction "2_2") (pintype "passive"))
    )
    (net (code "71") (name "Net-(JP18-Pad1)") (class "Default")
      (node (ref "JP18") (pin "1") (pinfunction "1_1") (pintype "passive"))
      (node (ref "JP19") (pin "1") (pinfunction "1_1") (pintype "passive"))
    )
    (net (code "72") (name "Net-(JP18-Pad2)") (class "Default")
      (node (ref "JP18") (pin "2") (pinfunction "2_2") (pintype "passive"))
      (node (ref "JP19") (pin "2") (pinfunction "2_2") (pintype "passive"))
    )
    (net (code "73") (name "Net-(JP20-Pad1)") (class "Default")
      (node (ref "JP20") (pin "1") (pinfunction "1_1") (pintype "passive"))
      (node (ref "JP23") (pin "1") (pinfunction "1_1") (pintype "passive"))
    )
    (net (code "74") (name "Net-(JP20-Pad2)") (class "Default")
      (node (ref "JP20") (pin "2") (pinfunction "2_2") (pintype "passive"))
      (node (ref "JP23") (pin "2") (pinfunction "2_2") (pintype "passive"))
    )
    (net (code "75") (name "Net-(JP21-Pad1)") (class "Default")
      (node (ref "JP21") (pin "1") (pinfunction "1_1") (pintype "passive"))
      (node (ref "JP24") (pin "1") (pinfunction "1_1") (pintype "passive"))
    )
    (net (code "76") (name "Net-(JP21-Pad2)") (class "Default")
      (node (ref "JP21") (pin "2") (pinfunction "2_2") (pintype "passive"))
      (node (ref "JP24") (pin "2") (pinfunction "2_2") (pintype "passive"))
    )
    (net (code "77") (name "Net-(JP22-Pad1)") (class "Default")
      (node (ref "JP22") (pin "1") (pinfunction "1_1") (pintype "passive"))
      (node (ref "JP25") (pin "1") (pinfunction "1_1") (pintype "passive"))
    )
    (net (code "78") (name "Net-(JP22-Pad2)") (class "Default")
      (node (ref "JP22") (pin "2") (pinfunction "2_2") (pintype "passive"))
      (node (ref "JP25") (pin "2") (pinfunction "2_2") (pintype "passive"))
    )
    (net (code "79") (name "Net-(JP26-Pad1)") (class "Default")
      (node (ref "JP26") (pin "1") (pinfunction "1_1") (pintype "passive"))
      (node (ref "JP27") (pin "1") (pinfunction "1_1") (pintype "passive"))
    )
    (net (code "80") (name "Net-(JP26-Pad2)") (class "Default")
      (node (ref "JP26") (pin "2") (pinfunction "2_2") (pintype "passive"))
      (node (ref "JP27") (pin "2") (pinfunction "2_2") (pintype "passive"))
    )
    (net (code "81") (name "Net-(JP28-Pad1)") (class "Default")
      (node (ref "JP28") (pin "1") (pinfunction "1_1") (pintype "passive"))
      (node (ref "JP29") (pin "1") (pinfunction "1_1") (pintype "passive"))
    )
    (net (code "82") (name "Net-(JP28-Pad2)") (class "Default")
      (node (ref "JP28") (pin "2") (pinfunction "2_2") (pintype "passive"))
      (node (ref "JP29") (pin "2") (pinfunction "2_2") (pintype "passive"))
    )
    (net (code "83") (name "Net-(JP30-Pad1)") (class "Default")
      (node (ref "JP30") (pin "1") (pinfunction "1_1") (pintype "passive"))
      (node (ref "JP31") (pin "1") (pinfunction "1_1") (pintype "passive"))
    )
    (net (code "84") (name "Net-(JP30-Pad2)") (class "Default")
      (node (ref "JP30") (pin "2") (pinfunction "2_2") (pintype "passive"))
      (node (ref "JP31") (pin "2") (pinfunction "2_2") (pintype "passive"))
    )
    (net (code "85") (name "Net-(JP32-Pad1)") (class "Default")
      (node (ref "JP32") (pin "1") (pinfunction "1_1") (pintype "passive"))
      (node (ref "JP33") (pin "1") (pinfunction "1_1") (pintype "passive"))
    )
    (net (code "86") (name "Net-(LED1-PadA)") (class "Default")
      (node (ref "LED1") (pin "A") (pinfunction "A_A") (pintype "passive"))
      (node (ref "R1") (pin "2") (pinfunction "2_2") (pintype "passive"))
    )
    (net (code "87") (name "Net-(LED1-PadC)") (class "Default")
      (node (ref "LED1") (pin "C") (pinfunction "C_C") (pintype "passive"))
      (node (ref "RED") (pin "1") (pinfunction "1_1") (pintype "passive"))
    )
    (net (code "88") (name "Net-(LED2-PadA)") (class "Default")
      (node (ref "LED2") (pin "A") (pinfunction "A_A") (pintype "passive"))
      (node (ref "R2") (pin "2") (pinfunction "2_2") (pintype "passive"))
    )
    (net (code "89") (name "Net-(R20-Pad2)") (class "Default")
      (node (ref "R20") (pin "2") (pinfunction "2_2") (pintype "passive"))
      (node (ref "SJ1") (pin "2") (pinfunction "2_2") (pintype "passive"))
    )
    (net (code "90") (name "Net-(R22-Pad2)") (class "Default")
      (node (ref "R22") (pin "2") (pinfunction "2_2") (pintype "passive"))
      (node (ref "SJ3") (pin "2") (pinfunction "2_2") (pintype "passive"))
    )
    (net (code "91") (name "Net-(U$7-RS)") (class "Default")
      (node (ref "R19") (pin "2") (pinfunction "2_2") (pintype "passive"))
      (node (ref "U$7") (pin "PIN8") (pinfunction "RS_PIN8") (pintype "bidirectional"))
    )
    (net (code "92") (name "Net-(U$8-RS)") (class "Default")
      (node (ref "R21") (pin "2") (pinfunction "2_2") (pintype "passive"))
      (node (ref "U$8") (pin "PIN8") (pinfunction "RS_PIN8") (pintype "bidirectional"))
    )
    (net (code "93") (name "unconnected-(U$1-Pad4)") (class "Default")
      (node (ref "U$1") (pin "4") (pinfunction "4_4") (pintype "bidirectional"))
    )
    (net (code "94") (name "unconnected-(U$1-Pad5)") (class "Default")
      (node (ref "U$1") (pin "5") (pinfunction "5_5") (pintype "bidirectional"))
    )
    (net (code "95") (name "unconnected-(U$1-Pad6)") (class "Default")
      (node (ref "U$1") (pin "6") (pinfunction "6_6") (pintype "bidirectional"))
    )
    (net (code "96") (name "unconnected-(U$1-Pad8)") (class "Default")
      (node (ref "U$1") (pin "8") (pinfunction "8_8") (pintype "bidirectional"))
    )
    (net (code "97") (name "unconnected-(U$2-Pad4)") (class "Default")
      (node (ref "U$2") (pin "4") (pinfunction "4_4") (pintype "bidirectional"))
    )
    (net (code "98") (name "unconnected-(U$2-Pad5)") (class "Default")
      (node (ref "U$2") (pin "5") (pinfunction "5_5") (pintype "bidirectional"))
    )
    (net (code "99") (name "unconnected-(U$2-Pad6)") (class "Default")
      (node (ref "U$2") (pin "6") (pinfunction "6_6") (pintype "bidirectional"))
    )
    (net (code "100") (name "unconnected-(U$2-Pad8)") (class "Default")
      (node (ref "U$2") (pin "8") (pinfunction "8_8") (pintype "bidirectional"))
    )
    (net (code "101") (name "unconnected-(U$3-CANH-PadPIN7)") (class "Default")
      (node (ref "U$3") (pin "PIN7") (pinfunction "CANH_PIN7") (pintype "bidirectional"))
    )
    (net (code "102") (name "unconnected-(U$3-CANL-PadPIN6)") (class "Default")
      (node (ref "U$3") (pin "PIN6") (pinfunction "CANL_PIN6") (pintype "bidirectional"))
    )
    (net (code "103") (name "unconnected-(U$3-D-PadPIN1)") (class "Default")
      (node (ref "U$3") (pin "PIN1") (pinfunction "D_PIN1") (pintype "bidirectional"))
    )
    (net (code "104") (name "unconnected-(U$3-EN-PadPIN5)") (class "Default")
      (node (ref "U$3") (pin "PIN5") (pinfunction "EN_PIN5") (pintype "bidirectional"))
    )
    (net (code "105") (name "unconnected-(U$3-GND-PadPIN2)") (class "Default")
      (node (ref "U$3") (pin "PIN2") (pinfunction "GND_PIN2") (pintype "bidirectional"))
    )
    (net (code "106") (name "unconnected-(U$3-R-PadPIN4)") (class "Default")
      (node (ref "U$3") (pin "PIN4") (pinfunction "R_PIN4") (pintype "bidirectional"))
    )
    (net (code "107") (name "unconnected-(U$3-RS-PadPIN8)") (class "Default")
      (node (ref "U$3") (pin "PIN8") (pinfunction "RS_PIN8") (pintype "bidirectional"))
    )
    (net (code "108") (name "unconnected-(U$3-VCC-PadPIN3)") (class "Default")
      (node (ref "U$3") (pin "PIN3") (pinfunction "VCC_PIN3") (pintype "bidirectional"))
    )
    (net (code "109") (name "unconnected-(U$4-CANH-PadPIN7)") (class "Default")
      (node (ref "U$4") (pin "PIN7") (pinfunction "CANH_PIN7") (pintype "bidirectional"))
    )
    (net (code "110") (name "unconnected-(U$4-CANL-PadPIN6)") (class "Default")
      (node (ref "U$4") (pin "PIN6") (pinfunction "CANL_PIN6") (pintype "bidirectional"))
    )
    (net (code "111") (name "unconnected-(U$4-D-PadPIN1)") (class "Default")
      (node (ref "U$4") (pin "PIN1") (pinfunction "D_PIN1") (pintype "bidirectional"))
    )
    (net (code "112") (name "unconnected-(U$4-EN-PadPIN5)") (class "Default")
      (node (ref "U$4") (pin "PIN5") (pinfunction "EN_PIN5") (pintype "bidirectional"))
    )
    (net (code "113") (name "unconnected-(U$4-GND-PadPIN2)") (class "Default")
      (node (ref "U$4") (pin "PIN2") (pinfunction "GND_PIN2") (pintype "bidirectional"))
    )
    (net (code "114") (name "unconnected-(U$4-R-PadPIN4)") (class "Default")
      (node (ref "U$4") (pin "PIN4") (pinfunction "R_PIN4") (pintype "bidirectional"))
    )
    (net (code "115") (name "unconnected-(U$4-RS-PadPIN8)") (class "Default")
      (node (ref "U$4") (pin "PIN8") (pinfunction "RS_PIN8") (pintype "bidirectional"))
    )
    (net (code "116") (name "unconnected-(U$4-VCC-PadPIN3)") (class "Default")
      (node (ref "U$4") (pin "PIN3") (pinfunction "VCC_PIN3") (pintype "bidirectional"))
    )
  )
)
